# TG16_buffer.net
KiCad netlist of a schematic drawn in EAGLE
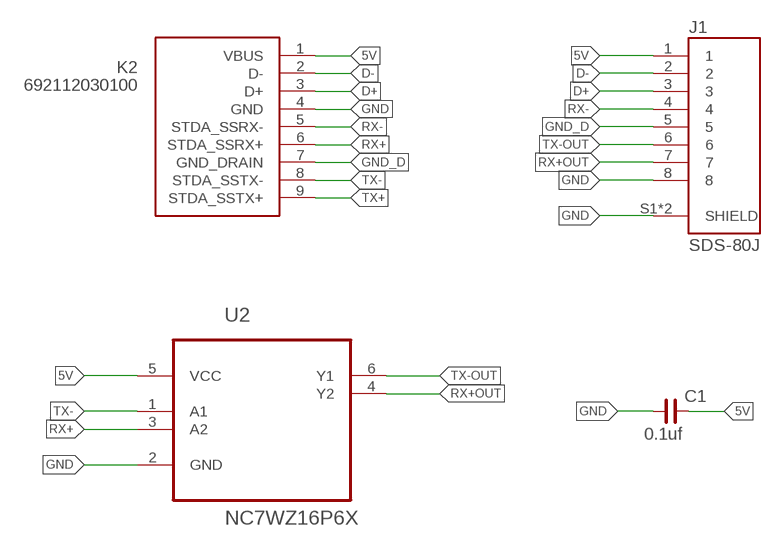
[diagram p0: schematic, sheet 1]

(export (version "E")
  (design (tool "Eeschema 10.0.6"))
  (components
    (comp (ref "C1")
      (value "0.1uf")
      (footprint "eagle-import:C0805")
      (libsource (lib "eagle-import") (part "C_0805"))
    )
    (comp (ref "J1")
      (value "SDS-80J")
      (footprint "eagle-import:CUI_SDS-80J")
      (fields (field (name "MF") "CUI Inc."))
      (libsource (lib "eagle-import") (part "SDS-80J"))
    )
    (comp (ref "K2")
      (value "692112030100")
      (footprint "eagle-import:692112030100")
      (libsource (lib "eagle-import") (part "692112030100"))
    )
    (comp (ref "U2")
      (value "NC7WZ16P6X")
      (footprint "eagle-import:SOT65P210X110-6N")
      (fields (field (name "MF") "ON Semiconductor"))
      (libsource (lib "eagle-import") (part "NC7WZ16P6X"))
    )
  )
  (nets
    (net (code "1") (name "5V") (class "Default")
      (node (ref "C1") (pin "2") (pinfunction "2_2") (pintype "passive"))
      (node (ref "J1") (pin "1") (pinfunction "1_1") (pintype "passive"))
      (node (ref "K2") (pin "1") (pinfunction "VBUS_1") (pintype "bidirectional"))
      (node (ref "U2") (pin "5") (pinfunction "VCC_5") (pintype "power_in"))
    )
    (net (code "2") (name "D+") (class "Default")
      (node (ref "J1") (pin "3") (pinfunction "3_3") (pintype "passive"))
      (node (ref "K2") (pin "3") (pinfunction "D+_3") (pintype "bidirectional"))
    )
    (net (code "3") (name "D-") (class "Default")
      (node (ref "J1") (pin "2") (pinfunction "2_2") (pintype "passive"))
      (node (ref "K2") (pin "2") (pinfunction "D-_2") (pintype "bidirectional"))
    )
    (net (code "4") (name "GND") (class "Default")
      (node (ref "C1") (pin "1") (pinfunction "1_1") (pintype "passive"))
      (node (ref "J1") (pin "8") (pinfunction "8_8") (pintype "passive"))
      (node (ref "J1") (pin "S1") (pinfunction "SHIELD_S1") (pintype "passive"))
      (node (ref "J1") (pin "S2") (pinfunction "SHIELD_S2") (pintype "passive"))
      (node (ref "K2") (pin "4") (pinfunction "GND_4") (pintype "bidirectional"))
      (node (ref "U2") (pin "2") (pinfunction "GND_2") (pintype "passive"))
    )
    (net (code "5") (name "GND_D") (class "Default")
      (node (ref "J1") (pin "5") (pinfunction "5_5") (pintype "passive"))
      (node (ref "K2") (pin "7") (pinfunction "GND_DRAIN_7") (pintype "bidirectional"))
    )
    (net (code "6") (name "RX+") (class "Default")
      (node (ref "K2") (pin "6") (pinfunction "STDA_SSRX+_6") (pintype "bidirectional"))
      (node (ref "U2") (pin "3") (pinfunction "A2_3") (pintype "input"))
    )
    (net (code "7") (name "RX+OUT") (class "Default")
      (node (ref "J1") (pin "7") (pinfunction "7_7") (pintype "passive"))
      (node (ref "U2") (pin "4") (pinfunction "Y2_4") (pintype "output"))
    )
    (net (code "8") (name "RX-") (class "Default")
      (node (ref "J1") (pin "4") (pinfunction "4_4") (pintype "passive"))
      (node (ref "K2") (pin "5") (pinfunction "STDA_SSRX-_5") (pintype "bidirectional"))
    )
    (net (code "9") (name "TX+") (class "Default")
      (node (ref "K2") (pin "9") (pinfunction "STDA_SSTX+_9") (pintype "bidirectional"))
    )
    (net (code "10") (name "TX-") (class "Default")
      (node (ref "K2") (pin "8") (pinfunction "STDA_SSTX-_8") (pintype "bidirectional"))
      (node (ref "U2") (pin "1") (pinfunction "A1_1") (pintype "input"))
    )
    (net (code "11") (name "TX-OUT") (class "Default")
      (node (ref "J1") (pin "6") (pinfunction "6_6") (pintype "passive"))
      (node (ref "U2") (pin "6") (pinfunction "Y1_6") (pintype "output"))
    )
  )
)
